# daughterboardFunkySwitch.net
KiCad netlist of a schematic drawn in Altium Designer
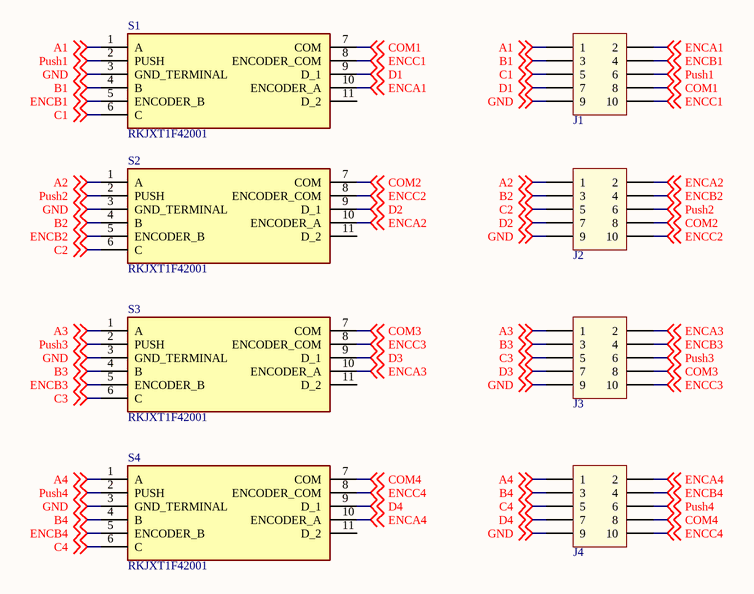
[diagram p0: daughterboardFunkySwitch.SchDoc]

(export (version "E")
  (design (tool "Eeschema 10.0.6"))
  (components
    (comp (ref "J1")
      (value "61301021821")
      (footprint "61301021821")
      (description "WR-PHD 2.54 mm Dual Socket Header, 10p")
      (fields (field (name "PUBLISHER") "Wurth Elektronik"))
      (libsource (lib "ALTIUM-PHD_2_54_DUAL_SOCKET_HEADER_6130XX21821") (part "61301021821"))
    )
    (comp (ref "J2")
      (value "61301021821")
      (footprint "61301021821")
      (description "WR-PHD 2.54 mm Dual Socket Header, 10p")
      (fields (field (name "PUBLISHER") "Wurth Elektronik"))
      (libsource (lib "ALTIUM-PHD_2_54_DUAL_SOCKET_HEADER_6130XX21821") (part "61301021821"))
    )
    (comp (ref "J3")
      (value "61301021821")
      (footprint "61301021821")
      (description "WR-PHD 2.54 mm Dual Socket Header, 10p")
      (fields (field (name "PUBLISHER") "Wurth Elektronik"))
      (libsource (lib "ALTIUM-PHD_2_54_DUAL_SOCKET_HEADER_6130XX21821") (part "61301021821"))
    )
    (comp (ref "J4")
      (value "61301021821")
      (footprint "61301021821")
      (description "WR-PHD 2.54 mm Dual Socket Header, 10p")
      (fields (field (name "PUBLISHER") "Wurth Elektronik"))
      (libsource (lib "ALTIUM-PHD_2_54_DUAL_SOCKET_HEADER_6130XX21821") (part "61301021821"))
    )
    (comp (ref "S1")
      (value "RKJXT1F42001")
      (footprint "RKJXT1F42001")
      (description "Switch")
      (fields (field (name "MOUSER2 PART NUMBER") "688-RKJXT1F42001"))
      (libsource (lib "Eric") (part "RKJXT1F42001"))
    )
    (comp (ref "S2")
      (value "RKJXT1F42001")
      (footprint "RKJXT1F42001")
      (description "Switch")
      (fields (field (name "MOUSER2 PART NUMBER") "688-RKJXT1F42001"))
      (libsource (lib "Eric") (part "RKJXT1F42001"))
    )
    (comp (ref "S3")
      (value "RKJXT1F42001")
      (footprint "RKJXT1F42001")
      (description "Switch")
      (fields (field (name "MOUSER2 PART NUMBER") "688-RKJXT1F42001"))
      (libsource (lib "Eric") (part "RKJXT1F42001"))
    )
    (comp (ref "S4")
      (value "RKJXT1F42001")
      (footprint "RKJXT1F42001")
      (description "Switch")
      (fields (field (name "MOUSER2 PART NUMBER") "688-RKJXT1F42001"))
      (libsource (lib "Eric") (part "RKJXT1F42001"))
    )
  )
  (nets
    (net (code "1") (name "A1") (class "Default")
      (node (ref "J1") (pin "1") (pinfunction "1_1") (pintype "passive"))
      (node (ref "S1") (pin "1") (pinfunction "A_1") (pintype "passive"))
    )
    (net (code "2") (name "A2") (class "Default")
      (node (ref "J2") (pin "1") (pinfunction "1_1") (pintype "passive"))
      (node (ref "S2") (pin "1") (pinfunction "A_1") (pintype "passive"))
    )
    (net (code "3") (name "A3") (class "Default")
      (node (ref "J3") (pin "1") (pinfunction "1_1") (pintype "passive"))
      (node (ref "S3") (pin "1") (pinfunction "A_1") (pintype "passive"))
    )
    (net (code "4") (name "A4") (class "Default")
      (node (ref "J4") (pin "1") (pinfunction "1_1") (pintype "passive"))
      (node (ref "S4") (pin "1") (pinfunction "A_1") (pintype "passive"))
    )
    (net (code "5") (name "B1") (class "Default")
      (node (ref "J1") (pin "3") (pinfunction "3_3") (pintype "passive"))
      (node (ref "S1") (pin "4") (pinfunction "B_4") (pintype "passive"))
    )
    (net (code "6") (name "B2") (class "Default")
      (node (ref "J2") (pin "3") (pinfunction "3_3") (pintype "passive"))
      (node (ref "S2") (pin "4") (pinfunction "B_4") (pintype "passive"))
    )
    (net (code "7") (name "B3") (class "Default")
      (node (ref "J3") (pin "3") (pinfunction "3_3") (pintype "passive"))
      (node (ref "S3") (pin "4") (pinfunction "B_4") (pintype "passive"))
    )
    (net (code "8") (name "B4") (class "Default")
      (node (ref "J4") (pin "3") (pinfunction "3_3") (pintype "passive"))
      (node (ref "S4") (pin "4") (pinfunction "B_4") (pintype "passive"))
    )
    (net (code "9") (name "C1") (class "Default")
      (node (ref "J1") (pin "5") (pinfunction "5_5") (pintype "passive"))
      (node (ref "S1") (pin "6") (pinfunction "C_6") (pintype "passive"))
    )
    (net (code "10") (name "C2") (class "Default")
      (node (ref "J2") (pin "5") (pinfunction "5_5") (pintype "passive"))
      (node (ref "S2") (pin "6") (pinfunction "C_6") (pintype "passive"))
    )
    (net (code "11") (name "C3") (class "Default")
      (node (ref "J3") (pin "5") (pinfunction "5_5") (pintype "passive"))
      (node (ref "S3") (pin "6") (pinfunction "C_6") (pintype "passive"))
    )
    (net (code "12") (name "C4") (class "Default")
      (node (ref "J4") (pin "5") (pinfunction "5_5") (pintype "passive"))
      (node (ref "S4") (pin "6") (pinfunction "C_6") (pintype "passive"))
    )
    (net (code "13") (name "COM1") (class "Default")
      (node (ref "J1") (pin "8") (pinfunction "8_8") (pintype "passive"))
      (node (ref "S1") (pin "7") (pinfunction "COM_7") (pintype "passive"))
    )
    (net (code "14") (name "COM2") (class "Default")
      (node (ref "J2") (pin "8") (pinfunction "8_8") (pintype "passive"))
      (node (ref "S2") (pin "7") (pinfunction "COM_7") (pintype "passive"))
    )
    (net (code "15") (name "COM3") (class "Default")
      (node (ref "J3") (pin "8") (pinfunction "8_8") (pintype "passive"))
      (node (ref "S3") (pin "7") (pinfunction "COM_7") (pintype "passive"))
    )
    (net (code "16") (name "COM4") (class "Default")
      (node (ref "J4") (pin "8") (pinfunction "8_8") (pintype "passive"))
      (node (ref "S4") (pin "7") (pinfunction "COM_7") (pintype "passive"))
    )
    (net (code "17") (name "D1") (class "Default")
      (node (ref "J1") (pin "7") (pinfunction "7_7") (pintype "passive"))
      (node (ref "S1") (pin "9") (pinfunction "D_1_9") (pintype "passive"))
    )
    (net (code "18") (name "D2") (class "Default")
      (node (ref "J2") (pin "7") (pinfunction "7_7") (pintype "passive"))
      (node (ref "S2") (pin "9") (pinfunction "D_1_9") (pintype "passive"))
    )
    (net (code "19") (name "D3") (class "Default")
      (node (ref "J3") (pin "7") (pinfunction "7_7") (pintype "passive"))
      (node (ref "S3") (pin "9") (pinfunction "D_1_9") (pintype "passive"))
    )
    (net (code "20") (name "D4") (class "Default")
      (node (ref "J4") (pin "7") (pinfunction "7_7") (pintype "passive"))
      (node (ref "S4") (pin "9") (pinfunction "D_1_9") (pintype "passive"))
    )
    (net (code "21") (name "ENCA1") (class "Default")
      (node (ref "J1") (pin "2") (pinfunction "2_2") (pintype "passive"))
      (node (ref "S1") (pin "10") (pinfunction "ENCODER_A_10") (pintype "passive"))
    )
    (net (code "22") (name "ENCA2") (class "Default")
      (node (ref "J2") (pin "2") (pinfunction "2_2") (pintype "passive"))
      (node (ref "S2") (pin "10") (pinfunction "ENCODER_A_10") (pintype "passive"))
    )
    (net (code "23") (name "ENCA3") (class "Default")
      (node (ref "J3") (pin "2") (pinfunction "2_2") (pintype "passive"))
      (node (ref "S3") (pin "10") (pinfunction "ENCODER_A_10") (pintype "passive"))
    )
    (net (code "24") (name "ENCA4") (class "Default")
      (node (ref "J4") (pin "2") (pinfunction "2_2") (pintype "passive"))
      (node (ref "S4") (pin "10") (pinfunction "ENCODER_A_10") (pintype "passive"))
    )
    (net (code "25") (name "ENCB1") (class "Default")
      (node (ref "J1") (pin "4") (pinfunction "4_4") (pintype "passive"))
      (node (ref "S1") (pin "5") (pinfunction "ENCODER_B_5") (pintype "passive"))
    )
    (net (code "26") (name "ENCB2") (class "Default")
      (node (ref "J2") (pin "4") (pinfunction "4_4") (pintype "passive"))
      (node (ref "S2") (pin "5") (pinfunction "ENCODER_B_5") (pintype "passive"))
    )
    (net (code "27") (name "ENCB3") (class "Default")
      (node (ref "J3") (pin "4") (pinfunction "4_4") (pintype "passive"))
      (node (ref "S3") (pin "5") (pinfunction "ENCODER_B_5") (pintype "passive"))
    )
    (net (code "28") (name "ENCB4") (class "Default")
      (node (ref "J4") (pin "4") (pinfunction "4_4") (pintype "passive"))
      (node (ref "S4") (pin "5") (pinfunction "ENCODER_B_5") (pintype "passive"))
    )
    (net (code "29") (name "ENCC1") (class "Default")
      (node (ref "J1") (pin "10") (pinfunction "10_10") (pintype "passive"))
      (node (ref "S1") (pin "8") (pinfunction "ENCODER_COM_8") (pintype "passive"))
    )
    (net (code "30") (name "ENCC2") (class "Default")
      (node (ref "J2") (pin "10") (pinfunction "10_10") (pintype "passive"))
      (node (ref "S2") (pin "8") (pinfunction "ENCODER_COM_8") (pintype "passive"))
    )
    (net (code "31") (name "ENCC3") (class "Default")
      (node (ref "J3") (pin "10") (pinfunction "10_10") (pintype "passive"))
      (node (ref "S3") (pin "8") (pinfunction "ENCODER_COM_8") (pintype "passive"))
    )
    (net (code "32") (name "ENCC4") (class "Default")
      (node (ref "J4") (pin "10") (pinfunction "10_10") (pintype "passive"))
      (node (ref "S4") (pin "8") (pinfunction "ENCODER_COM_8") (pintype "passive"))
    )
    (net (code "33") (name "GND") (class "Default")
      (node (ref "J1") (pin "9") (pinfunction "9_9") (pintype "passive"))
      (node (ref "J2") (pin "9") (pinfunction "9_9") (pintype "passive"))
      (node (ref "J3") (pin "9") (pinfunction "9_9") (pintype "passive"))
      (node (ref "J4") (pin "9") (pinfunction "9_9") (pintype "passive"))
      (node (ref "S1") (pin "3") (pinfunction "GND_TERMINAL_3") (pintype "passive"))
      (node (ref "S2") (pin "3") (pinfunction "GND_TERMINAL_3") (pintype "passive"))
      (node (ref "S3") (pin "3") (pinfunction "GND_TERMINAL_3") (pintype "passive"))
      (node (ref "S4") (pin "3") (pinfunction "GND_TERMINAL_3") (pintype "passive"))
    )
    (net (code "34") (name "Push1") (class "Default")
      (node (ref "J1") (pin "6") (pinfunction "6_6") (pintype "passive"))
      (node (ref "S1") (pin "2") (pinfunction "PUSH_2") (pintype "passive"))
    )
    (net (code "35") (name "Push2") (class "Default")
      (node (ref "J2") (pin "6") (pinfunction "6_6") (pintype "passive"))
      (node (ref "S2") (pin "2") (pinfunction "PUSH_2") (pintype "passive"))
    )
    (net (code "36") (name "Push3") (class "Default")
      (node (ref "J3") (pin "6") (pinfunction "6_6") (pintype "passive"))
      (node (ref "S3") (pin "2") (pinfunction "PUSH_2") (pintype "passive"))
    )
    (net (code "37") (name "Push4") (class "Default")
      (node (ref "J4") (pin "6") (pinfunction "6_6") (pintype "passive"))
      (node (ref "S4") (pin "2") (pinfunction "PUSH_2") (pintype "passive"))
    )
    (net (code "38") (name "unconnected-(S1-D_2-Pad11)") (class "Default")
      (node (ref "S1") (pin "11") (pinfunction "D_2_11") (pintype "passive"))
    )
    (net (code "39") (name "unconnected-(S2-D_2-Pad11)") (class "Default")
      (node (ref "S2") (pin "11") (pinfunction "D_2_11") (pintype "passive"))
    )
    (net (code "40") (name "unconnected-(S3-D_2-Pad11)") (class "Default")
      (node (ref "S3") (pin "11") (pinfunction "D_2_11") (pintype "passive"))
    )
    (net (code "41") (name "unconnected-(S4-D_2-Pad11)") (class "Default")
      (node (ref "S4") (pin "11") (pinfunction "D_2_11") (pintype "passive"))
    )
  )
)
